# Mother_Board_Connectors.net
KiCad netlist of a schematic drawn in Altium Designer
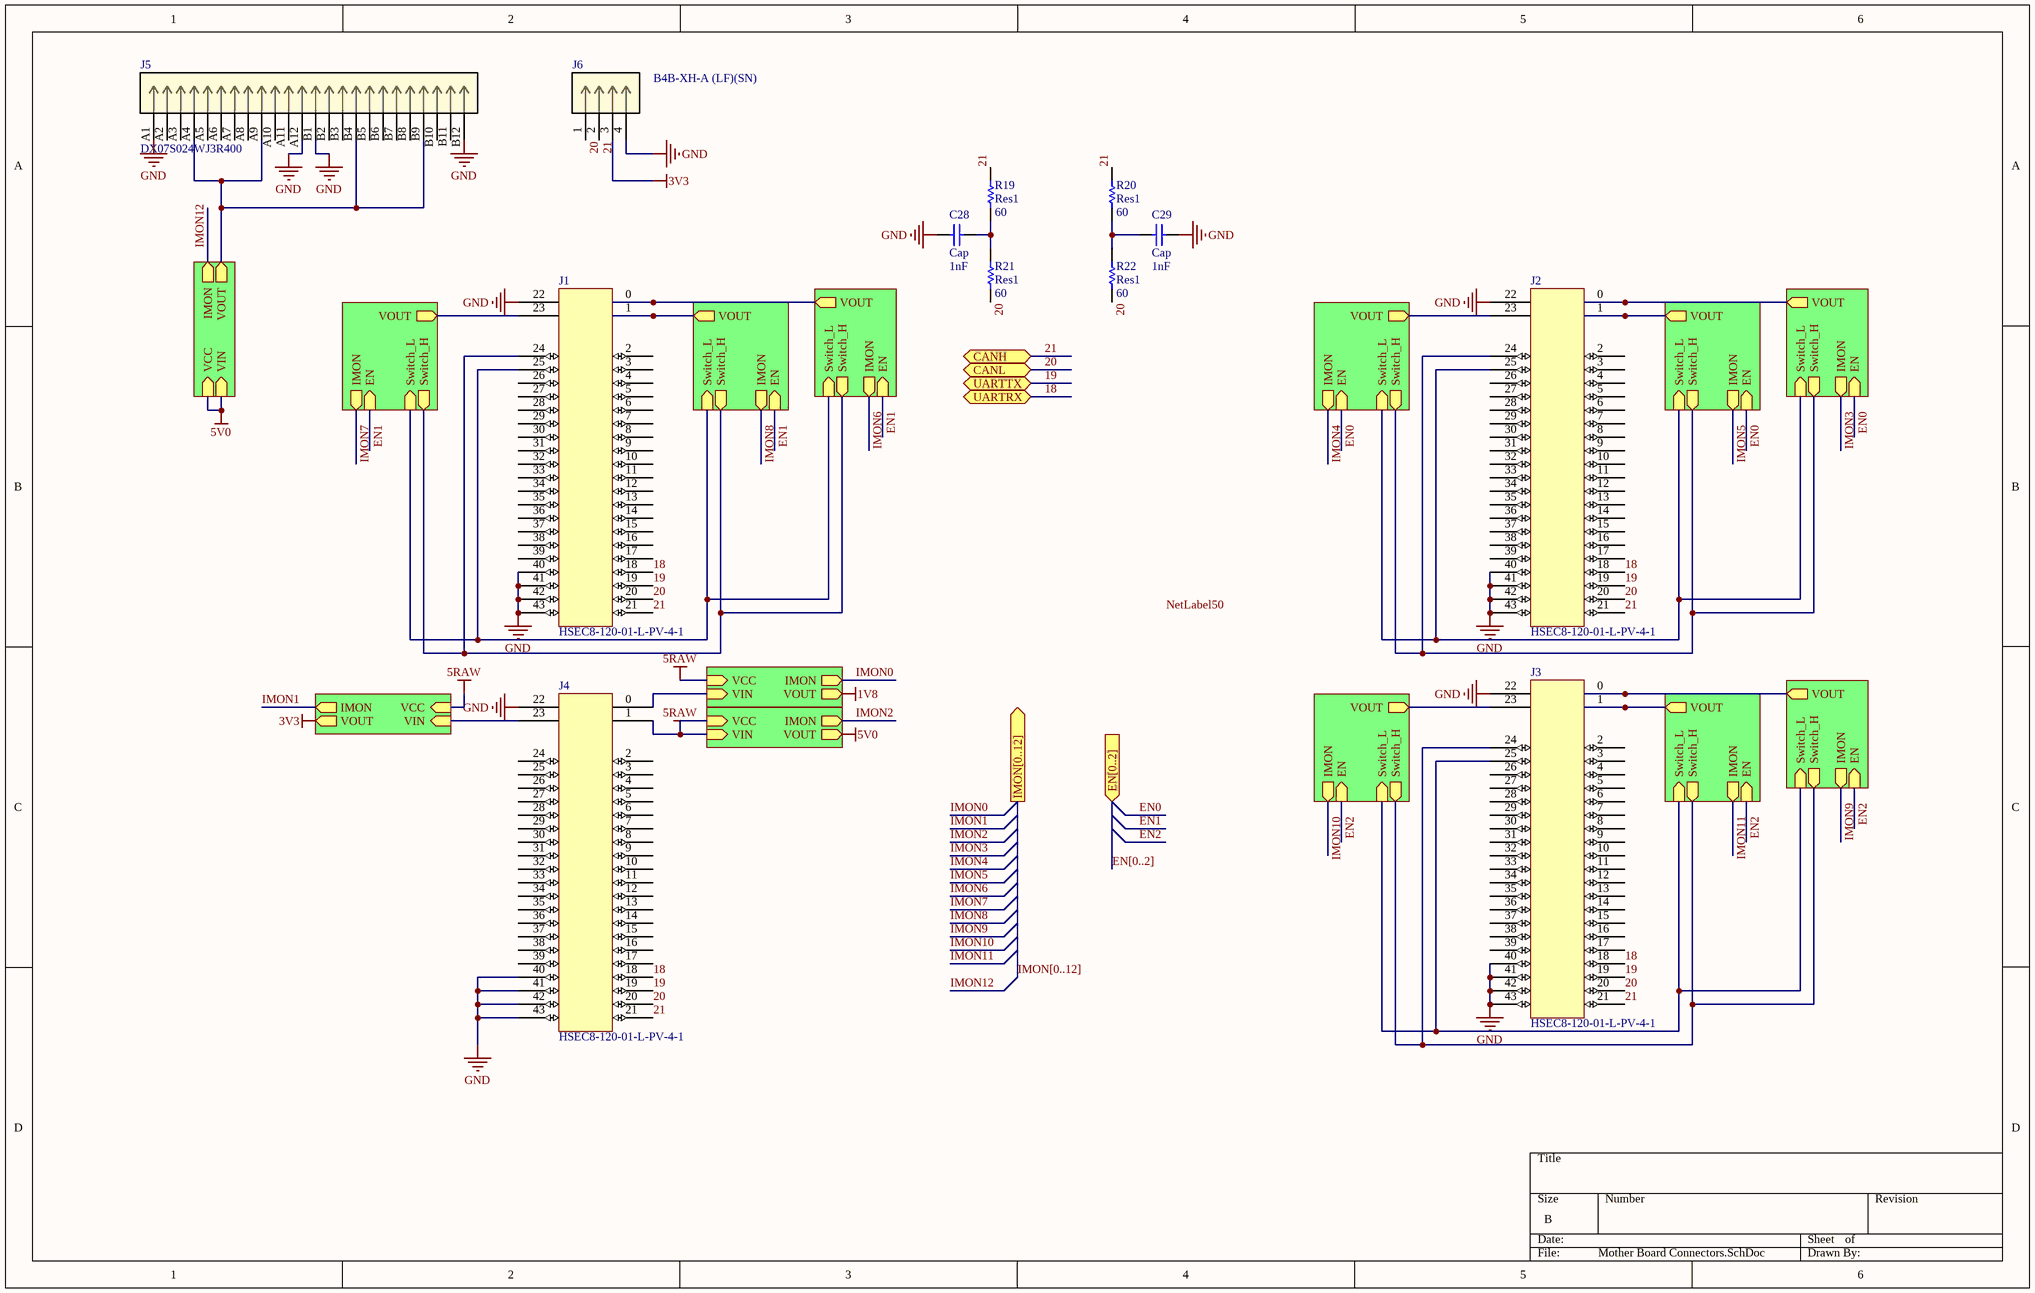
[diagram p0: Mother Board Connectors.SchDoc]

(export (version "E")
  (design (tool "Eeschema 10.0.6"))
  (components
    (comp (ref "C28")
      (value "Cap")
      (footprint "1608[0603]")
      (description "Capacitor")
      (fields (field (name "ALTIUM_VALUE") "1nF") (field (name "PUBLISHER") "Altium Limited"))
      (libsource (lib "Miscellaneous Devices") (part "Cap"))
    )
    (comp (ref "C29")
      (value "Cap")
      (footprint "1608[0603]")
      (description "Capacitor")
      (fields (field (name "ALTIUM_VALUE") "1nF") (field (name "PUBLISHER") "Altium Limited"))
      (libsource (lib "Miscellaneous Devices") (part "Cap"))
    )
    (comp (ref "J1")
      (value "HSEC8-120-01-L-PV-4-1")
      (footprint "HSEC8-120-01-L-PV-4-1")
      (libsource (lib "Edge Connector") (part "HSEC8-120-01-L-PV-4-1"))
    )
    (comp (ref "J2")
      (value "HSEC8-120-01-L-PV-4-1")
      (footprint "HSEC8-120-01-L-PV-4-1")
      (libsource (lib "Edge Connector") (part "HSEC8-120-01-L-PV-4-1"))
    )
    (comp (ref "J3")
      (value "HSEC8-120-01-L-PV-4-1")
      (footprint "HSEC8-120-01-L-PV-4-1")
      (libsource (lib "Edge Connector") (part "HSEC8-120-01-L-PV-4-1"))
    )
    (comp (ref "J4")
      (value "HSEC8-120-01-L-PV-4-1")
      (footprint "HSEC8-120-01-L-PV-4-1")
      (libsource (lib "Edge Connector") (part "HSEC8-120-01-L-PV-4-1"))
    )
    (comp (ref "J5")
      (value "DX07S024WJ3R400")
      (footprint "CONN_DX07S024WJ1R350_JAE")
      (description "No Description Available")
      (fields (field (name "COPYRIGHT") "Copyright (C) 2018 Accelerated Designs. All rights reserved"))
      (libsource (lib "DX07S024WJ3R400") (part "DX07S024WJ3R400"))
    )
    (comp (ref "J6")
      (value "B4B-XH-A (LF)(SN)")
      (footprint "CONN_B4B-XH-A (LF)(SN)_JST")
      (description "No Description Available")
      (fields (field (name "COPYRIGHT") "Copyright (C) 2018 Accelerated Designs. All rights reserved"))
      (libsource (lib "ABC motor conn") (part "B4B-XH-A (LF)(SN)"))
    )
    (comp (ref "R19")
      (value "Res1")
      (footprint "0402-A")
      (description "Resistor")
      (fields (field (name "ALTIUM_VALUE") "60") (field (name "PUBLISHER") "Altium Limited"))
      (libsource (lib "Miscellaneous Devices") (part "Res1"))
    )
    (comp (ref "R20")
      (value "Res1")
      (footprint "0402-A")
      (description "Resistor")
      (fields (field (name "ALTIUM_VALUE") "60") (field (name "PUBLISHER") "Altium Limited"))
      (libsource (lib "Miscellaneous Devices") (part "Res1"))
    )
    (comp (ref "R21")
      (value "Res1")
      (footprint "0402-A")
      (description "Resistor")
      (fields (field (name "ALTIUM_VALUE") "60") (field (name "PUBLISHER") "Altium Limited"))
      (libsource (lib "Miscellaneous Devices") (part "Res1"))
    )
    (comp (ref "R22")
      (value "Res1")
      (footprint "0402-A")
      (description "Resistor")
      (fields (field (name "ALTIUM_VALUE") "60") (field (name "PUBLISHER") "Altium Limited"))
      (libsource (lib "Miscellaneous Devices") (part "Res1"))
    )
  )
  (nets
    (net (code "1") (name "/18") (class "Default")
      (node (ref "J1") (pin "18") (pinfunction "0_18") (pintype "bidirectional"))
      (node (ref "J2") (pin "18") (pinfunction "0_18") (pintype "bidirectional"))
      (node (ref "J3") (pin "18") (pinfunction "0_18") (pintype "bidirectional"))
      (node (ref "J4") (pin "18") (pinfunction "0_18") (pintype "bidirectional"))
    )
    (net (code "2") (name "/19") (class "Default")
      (node (ref "J1") (pin "19") (pinfunction "0_19") (pintype "bidirectional"))
      (node (ref "J2") (pin "19") (pinfunction "0_19") (pintype "bidirectional"))
      (node (ref "J3") (pin "19") (pinfunction "0_19") (pintype "bidirectional"))
      (node (ref "J4") (pin "19") (pinfunction "0_19") (pintype "bidirectional"))
    )
    (net (code "3") (name "/20") (class "Default")
      (node (ref "J1") (pin "20") (pinfunction "0_20") (pintype "bidirectional"))
      (node (ref "J2") (pin "20") (pinfunction "0_20") (pintype "bidirectional"))
      (node (ref "J3") (pin "20") (pinfunction "0_20") (pintype "bidirectional"))
      (node (ref "J4") (pin "20") (pinfunction "0_20") (pintype "bidirectional"))
      (node (ref "J6") (pin "1") (pinfunction "1_1") (pintype "passive"))
      (node (ref "R21") (pin "1") (pinfunction "1_1") (pintype "passive"))
      (node (ref "R22") (pin "1") (pinfunction "1_1") (pintype "passive"))
    )
    (net (code "4") (name "/21") (class "Default")
      (node (ref "J1") (pin "21") (pinfunction "0_21") (pintype "bidirectional"))
      (node (ref "J2") (pin "21") (pinfunction "0_21") (pintype "bidirectional"))
      (node (ref "J3") (pin "21") (pinfunction "0_21") (pintype "bidirectional"))
      (node (ref "J4") (pin "21") (pinfunction "0_21") (pintype "bidirectional"))
      (node (ref "J6") (pin "2") (pinfunction "2_2") (pintype "passive"))
      (node (ref "R19") (pin "2") (pinfunction "2_2") (pintype "passive"))
      (node (ref "R20") (pin "2") (pinfunction "2_2") (pintype "passive"))
    )
    (net (code "24") (name "/Switch_H") (class "Default")
      (node (ref "J2") (pin "24") (pinfunction "24_24") (pintype "bidirectional"))
    )
    (net (code "25") (name "/Switch_H_1") (class "Default")
      (node (ref "J1") (pin "24") (pinfunction "24_24") (pintype "bidirectional"))
    )
    (net (code "26") (name "/Switch_H_2") (class "Default")
      (node (ref "J3") (pin "24") (pinfunction "24_24") (pintype "bidirectional"))
    )
    (net (code "27") (name "/Switch_L") (class "Default")
      (node (ref "J2") (pin "25") (pinfunction "25_25") (pintype "bidirectional"))
    )
    (net (code "28") (name "/Switch_L_1") (class "Default")
      (node (ref "J1") (pin "25") (pinfunction "25_25") (pintype "bidirectional"))
    )
    (net (code "29") (name "/Switch_L_2") (class "Default")
      (node (ref "J3") (pin "25") (pinfunction "25_25") (pintype "bidirectional"))
    )
    (net (code "30") (name "/VIN") (class "Default")
      (node (ref "J4") (pin "0") (pinfunction "0_0") (pintype "power_in"))
    )
    (net (code "31") (name "/VIN_1") (class "Default")
      (node (ref "J4") (pin "23") (pinfunction "23_23") (pintype "power_in"))
    )
    (net (code "32") (name "/VOUT") (class "Default")
      (node (ref "J1") (pin "0") (pinfunction "0_0") (pintype "power_in"))
    )
    (net (code "33") (name "/VOUT_1") (class "Default")
      (node (ref "J5") (pin "A4") (pinfunction "B11_A4") (pintype "passive"))
      (node (ref "J5") (pin "A9") (pinfunction "A5_A9") (pintype "passive"))
      (node (ref "J5") (pin "B4") (pinfunction "B5_B4") (pintype "passive"))
      (node (ref "J5") (pin "B9") (pinfunction "A11_B9") (pintype "passive"))
    )
    (net (code "34") (name "/VOUT_2") (class "Default")
      (node (ref "J3") (pin "23") (pinfunction "23_23") (pintype "power_in"))
    )
    (net (code "35") (name "/VOUT_3") (class "Default")
      (node (ref "J2") (pin "1") (pinfunction "0_1") (pintype "power_in"))
    )
    (net (code "36") (name "/VOUT_4") (class "Default")
      (node (ref "J3") (pin "1") (pinfunction "0_1") (pintype "power_in"))
    )
    (net (code "37") (name "/VOUT_5") (class "Default")
      (node (ref "J2") (pin "0") (pinfunction "0_0") (pintype "power_in"))
    )
    (net (code "38") (name "/VOUT_6") (class "Default")
      (node (ref "J3") (pin "0") (pinfunction "0_0") (pintype "power_in"))
    )
    (net (code "39") (name "/VOUT_7") (class "Default")
      (node (ref "J2") (pin "23") (pinfunction "23_23") (pintype "power_in"))
    )
    (net (code "40") (name "/VOUT_8") (class "Default")
      (node (ref "J1") (pin "23") (pinfunction "23_23") (pintype "power_in"))
    )
    (net (code "41") (name "/VOUT_9") (class "Default")
      (node (ref "J1") (pin "1") (pinfunction "0_1") (pintype "power_in"))
    )
    (net (code "43") (name "3V3") (class "Default")
      (node (ref "J6") (pin "3") (pinfunction "3_3") (pintype "passive"))
    )
    (net (code "44") (name "5RAW") (class "Default")
      (node (ref "J4") (pin "1") (pinfunction "0_1") (pintype "power_in"))
    )
    (net (code "46") (name "GND") (class "Default")
      (node (ref "C28") (pin "2") (pinfunction "2_2") (pintype "passive"))
      (node (ref "C29") (pin "1") (pinfunction "1_1") (pintype "passive"))
      (node (ref "J1") (pin "22") (pinfunction "0_22") (pintype "power_in"))
      (node (ref "J1") (pin "40") (pinfunction "40_40") (pintype "bidirectional"))
      (node (ref "J1") (pin "41") (pinfunction "41_41") (pintype "bidirectional"))
      (node (ref "J1") (pin "42") (pinfunction "42_42") (pintype "bidirectional"))
      (node (ref "J1") (pin "43") (pinfunction "43_43") (pintype "bidirectional"))
      (node (ref "J2") (pin "22") (pinfunction "0_22") (pintype "power_in"))
      (node (ref "J2") (pin "40") (pinfunction "40_40") (pintype "bidirectional"))
      (node (ref "J2") (pin "41") (pinfunction "41_41") (pintype "bidirectional"))
      (node (ref "J2") (pin "42") (pinfunction "42_42") (pintype "bidirectional"))
      (node (ref "J2") (pin "43") (pinfunction "43_43") (pintype "bidirectional"))
      (node (ref "J3") (pin "22") (pinfunction "0_22") (pintype "power_in"))
      (node (ref "J3") (pin "40") (pinfunction "40_40") (pintype "bidirectional"))
      (node (ref "J3") (pin "41") (pinfunction "41_41") (pintype "bidirectional"))
      (node (ref "J3") (pin "42") (pinfunction "42_42") (pintype "bidirectional"))
      (node (ref "J3") (pin "43") (pinfunction "43_43") (pintype "bidirectional"))
      (node (ref "J4") (pin "22") (pinfunction "0_22") (pintype "power_in"))
      (node (ref "J4") (pin "40") (pinfunction "40_40") (pintype "bidirectional"))
      (node (ref "J4") (pin "41") (pinfunction "41_41") (pintype "bidirectional"))
      (node (ref "J4") (pin "42") (pinfunction "42_42") (pintype "bidirectional"))
      (node (ref "J4") (pin "43") (pinfunction "43_43") (pintype "bidirectional"))
      (node (ref "J5") (pin "A1") (pinfunction "A1_A1") (pintype "passive"))
      (node (ref "J5") (pin "A12") (pinfunction "B7_A12") (pintype "passive"))
      (node (ref "J5") (pin "B1") (pinfunction "A7_B1") (pintype "passive"))
      (node (ref "J5") (pin "B12") (pinfunction "B1_B12") (pintype "passive"))
      (node (ref "J6") (pin "4") (pinfunction "4_4") (pintype "passive"))
    )
    (net (code "47") (name "Net-(C28-Pad1)") (class "Default")
      (node (ref "C28") (pin "1") (pinfunction "1_1") (pintype "passive"))
      (node (ref "R19") (pin "1") (pinfunction "1_1") (pintype "passive"))
      (node (ref "R21") (pin "2") (pinfunction "2_2") (pintype "passive"))
    )
    (net (code "48") (name "Net-(C29-Pad2)") (class "Default")
      (node (ref "C29") (pin "2") (pinfunction "2_2") (pintype "passive"))
      (node (ref "R20") (pin "1") (pinfunction "1_1") (pintype "passive"))
      (node (ref "R22") (pin "2") (pinfunction "2_2") (pintype "passive"))
    )
    (net (code "49") (name "unconnected-(J1-0-Pad2)") (class "Default")
      (node (ref "J1") (pin "2") (pinfunction "0_2") (pintype "bidirectional"))
    )
    (net (code "50") (name "unconnected-(J1-0-Pad3)") (class "Default")
      (node (ref "J1") (pin "3") (pinfunction "0_3") (pintype "bidirectional"))
    )
    (net (code "51") (name "unconnected-(J1-0-Pad4)") (class "Default")
      (node (ref "J1") (pin "4") (pinfunction "0_4") (pintype "bidirectional"))
    )
    (net (code "52") (name "unconnected-(J1-0-Pad5)") (class "Default")
      (node (ref "J1") (pin "5") (pinfunction "0_5") (pintype "bidirectional"))
    )
    (net (code "53") (name "unconnected-(J1-0-Pad6)") (class "Default")
      (node (ref "J1") (pin "6") (pinfunction "0_6") (pintype "bidirectional"))
    )
    (net (code "54") (name "unconnected-(J1-0-Pad7)") (class "Default")
      (node (ref "J1") (pin "7") (pinfunction "0_7") (pintype "bidirectional"))
    )
    (net (code "55") (name "unconnected-(J1-0-Pad8)") (class "Default")
      (node (ref "J1") (pin "8") (pinfunction "0_8") (pintype "bidirectional"))
    )
    (net (code "56") (name "unconnected-(J1-0-Pad9)") (class "Default")
      (node (ref "J1") (pin "9") (pinfunction "0_9") (pintype "bidirectional"))
    )
    (net (code "57") (name "unconnected-(J1-0-Pad10)") (class "Default")
      (node (ref "J1") (pin "10") (pinfunction "0_10") (pintype "bidirectional"))
    )
    (net (code "58") (name "unconnected-(J1-0-Pad11)") (class "Default")
      (node (ref "J1") (pin "11") (pinfunction "0_11") (pintype "bidirectional"))
    )
    (net (code "59") (name "unconnected-(J1-0-Pad12)") (class "Default")
      (node (ref "J1") (pin "12") (pinfunction "0_12") (pintype "bidirectional"))
    )
    (net (code "60") (name "unconnected-(J1-0-Pad13)") (class "Default")
      (node (ref "J1") (pin "13") (pinfunction "0_13") (pintype "bidirectional"))
    )
    (net (code "61") (name "unconnected-(J1-0-Pad14)") (class "Default")
      (node (ref "J1") (pin "14") (pinfunction "0_14") (pintype "bidirectional"))
    )
    (net (code "62") (name "unconnected-(J1-0-Pad15)") (class "Default")
      (node (ref "J1") (pin "15") (pinfunction "0_15") (pintype "bidirectional"))
    )
    (net (code "63") (name "unconnected-(J1-0-Pad16)") (class "Default")
      (node (ref "J1") (pin "16") (pinfunction "0_16") (pintype "bidirectional"))
    )
    (net (code "64") (name "unconnected-(J1-0-Pad17)") (class "Default")
      (node (ref "J1") (pin "17") (pinfunction "0_17") (pintype "bidirectional"))
    )
    (net (code "65") (name "unconnected-(J1-Pad26)") (class "Default")
      (node (ref "J1") (pin "26") (pinfunction "26_26") (pintype "bidirectional"))
    )
    (net (code "66") (name "unconnected-(J1-Pad27)") (class "Default")
      (node (ref "J1") (pin "27") (pinfunction "27_27") (pintype "bidirectional"))
    )
    (net (code "67") (name "unconnected-(J1-Pad28)") (class "Default")
      (node (ref "J1") (pin "28") (pinfunction "28_28") (pintype "bidirectional"))
    )
    (net (code "68") (name "unconnected-(J1-Pad29)") (class "Default")
      (node (ref "J1") (pin "29") (pinfunction "29_29") (pintype "bidirectional"))
    )
    (net (code "69") (name "unconnected-(J1-Pad30)") (class "Default")
      (node (ref "J1") (pin "30") (pinfunction "30_30") (pintype "bidirectional"))
    )
    (net (code "70") (name "unconnected-(J1-Pad31)") (class "Default")
      (node (ref "J1") (pin "31") (pinfunction "31_31") (pintype "bidirectional"))
    )
    (net (code "71") (name "unconnected-(J1-Pad32)") (class "Default")
      (node (ref "J1") (pin "32") (pinfunction "32_32") (pintype "bidirectional"))
    )
    (net (code "72") (name "unconnected-(J1-Pad33)") (class "Default")
      (node (ref "J1") (pin "33") (pinfunction "33_33") (pintype "bidirectional"))
    )
    (net (code "73") (name "unconnected-(J1-Pad34)") (class "Default")
      (node (ref "J1") (pin "34") (pinfunction "34_34") (pintype "bidirectional"))
    )
    (net (code "74") (name "unconnected-(J1-Pad35)") (class "Default")
      (node (ref "J1") (pin "35") (pinfunction "35_35") (pintype "bidirectional"))
    )
    (net (code "75") (name "unconnected-(J1-Pad36)") (class "Default")
      (node (ref "J1") (pin "36") (pinfunction "36_36") (pintype "bidirectional"))
    )
    (net (code "76") (name "unconnected-(J1-Pad37)") (class "Default")
      (node (ref "J1") (pin "37") (pinfunction "37_37") (pintype "bidirectional"))
    )
    (net (code "77") (name "unconnected-(J1-Pad38)") (class "Default")
      (node (ref "J1") (pin "38") (pinfunction "38_38") (pintype "bidirectional"))
    )
    (net (code "78") (name "unconnected-(J1-Pad39)") (class "Default")
      (node (ref "J1") (pin "39") (pinfunction "39_39") (pintype "bidirectional"))
    )
    (net (code "79") (name "unconnected-(J2-0-Pad2)") (class "Default")
      (node (ref "J2") (pin "2") (pinfunction "0_2") (pintype "bidirectional"))
    )
    (net (code "80") (name "unconnected-(J2-0-Pad3)") (class "Default")
      (node (ref "J2") (pin "3") (pinfunction "0_3") (pintype "bidirectional"))
    )
    (net (code "81") (name "unconnected-(J2-0-Pad4)") (class "Default")
      (node (ref "J2") (pin "4") (pinfunction "0_4") (pintype "bidirectional"))
    )
    (net (code "82") (name "unconnected-(J2-0-Pad5)") (class "Default")
      (node (ref "J2") (pin "5") (pinfunction "0_5") (pintype "bidirectional"))
    )
    (net (code "83") (name "unconnected-(J2-0-Pad6)") (class "Default")
      (node (ref "J2") (pin "6") (pinfunction "0_6") (pintype "bidirectional"))
    )
    (net (code "84") (name "unconnected-(J2-0-Pad7)") (class "Default")
      (node (ref "J2") (pin "7") (pinfunction "0_7") (pintype "bidirectional"))
    )
    (net (code "85") (name "unconnected-(J2-0-Pad8)") (class "Default")
      (node (ref "J2") (pin "8") (pinfunction "0_8") (pintype "bidirectional"))
    )
    (net (code "86") (name "unconnected-(J2-0-Pad9)") (class "Default")
      (node (ref "J2") (pin "9") (pinfunction "0_9") (pintype "bidirectional"))
    )
    (net (code "87") (name "unconnected-(J2-0-Pad10)") (class "Default")
      (node (ref "J2") (pin "10") (pinfunction "0_10") (pintype "bidirectional"))
    )
    (net (code "88") (name "unconnected-(J2-0-Pad11)") (class "Default")
      (node (ref "J2") (pin "11") (pinfunction "0_11") (pintype "bidirectional"))
    )
    (net (code "89") (name "unconnected-(J2-0-Pad12)") (class "Default")
      (node (ref "J2") (pin "12") (pinfunction "0_12") (pintype "bidirectional"))
    )
    (net (code "90") (name "unconnected-(J2-0-Pad13)") (class "Default")
      (node (ref "J2") (pin "13") (pinfunction "0_13") (pintype "bidirectional"))
    )
    (net (code "91") (name "unconnected-(J2-0-Pad14)") (class "Default")
      (node (ref "J2") (pin "14") (pinfunction "0_14") (pintype "bidirectional"))
    )
    (net (code "92") (name "unconnected-(J2-0-Pad15)") (class "Default")
      (node (ref "J2") (pin "15") (pinfunction "0_15") (pintype "bidirectional"))
    )
    (net (code "93") (name "unconnected-(J2-0-Pad16)") (class "Default")
      (node (ref "J2") (pin "16") (pinfunction "0_16") (pintype "bidirectional"))
    )
    (net (code "94") (name "unconnected-(J2-0-Pad17)") (class "Default")
      (node (ref "J2") (pin "17") (pinfunction "0_17") (pintype "bidirectional"))
    )
    (net (code "95") (name "unconnected-(J2-Pad26)") (class "Default")
      (node (ref "J2") (pin "26") (pinfunction "26_26") (pintype "bidirectional"))
    )
    (net (code "96") (name "unconnected-(J2-Pad27)") (class "Default")
      (node (ref "J2") (pin "27") (pinfunction "27_27") (pintype "bidirectional"))
    )
    (net (code "97") (name "unconnected-(J2-Pad28)") (class "Default")
      (node (ref "J2") (pin "28") (pinfunction "28_28") (pintype "bidirectional"))
    )
    (net (code "98") (name "unconnected-(J2-Pad29)") (class "Default")
      (node (ref "J2") (pin "29") (pinfunction "29_29") (pintype "bidirectional"))
    )
    (net (code "99") (name "unconnected-(J2-Pad30)") (class "Default")
      (node (ref "J2") (pin "30") (pinfunction "30_30") (pintype "bidirectional"))
    )
    (net (code "100") (name "unconnected-(J2-Pad31)") (class "Default")
      (node (ref "J2") (pin "31") (pinfunction "31_31") (pintype "bidirectional"))
    )
    (net (code "101") (name "unconnected-(J2-Pad32)") (class "Default")
      (node (ref "J2") (pin "32") (pinfunction "32_32") (pintype "bidirectional"))
    )
    (net (code "102") (name "unconnected-(J2-Pad33)") (class "Default")
      (node (ref "J2") (pin "33") (pinfunction "33_33") (pintype "bidirectional"))
    )
    (net (code "103") (name "unconnected-(J2-Pad34)") (class "Default")
      (node (ref "J2") (pin "34") (pinfunction "34_34") (pintype "bidirectional"))
    )
    (net (code "104") (name "unconnected-(J2-Pad35)") (class "Default")
      (node (ref "J2") (pin "35") (pinfunction "35_35") (pintype "bidirectional"))
    )
    (net (code "105") (name "unconnected-(J2-Pad36)") (class "Default")
      (node (ref "J2") (pin "36") (pinfunction "36_36") (pintype "bidirectional"))
    )
    (net (code "106") (name "unconnected-(J2-Pad37)") (class "Default")
      (node (ref "J2") (pin "37") (pinfunction "37_37") (pintype "bidirectional"))
    )
    (net (code "107") (name "unconnected-(J2-Pad38)") (class "Default")
      (node (ref "J2") (pin "38") (pinfunction "38_38") (pintype "bidirectional"))
    )
    (net (code "108") (name "unconnected-(J2-Pad39)") (class "Default")
      (node (ref "J2") (pin "39") (pinfunction "39_39") (pintype "bidirectional"))
    )
    (net (code "109") (name "unconnected-(J3-0-Pad2)") (class "Default")
      (node (ref "J3") (pin "2") (pinfunction "0_2") (pintype "bidirectional"))
    )
    (net (code "110") (name "unconnected-(J3-0-Pad3)") (class "Default")
      (node (ref "J3") (pin "3") (pinfunction "0_3") (pintype "bidirectional"))
    )
    (net (code "111") (name "unconnected-(J3-0-Pad4)") (class "Default")
      (node (ref "J3") (pin "4") (pinfunction "0_4") (pintype "bidirectional"))
    )
    (net (code "112") (name "unconnected-(J3-0-Pad5)") (class "Default")
      (node (ref "J3") (pin "5") (pinfunction "0_5") (pintype "bidirectional"))
    )
    (net (code "113") (name "unconnected-(J3-0-Pad6)") (class "Default")
      (node (ref "J3") (pin "6") (pinfunction "0_6") (pintype "bidirectional"))
    )
    (net (code "114") (name "unconnected-(J3-0-Pad7)") (class "Default")
      (node (ref "J3") (pin "7") (pinfunction "0_7") (pintype "bidirectional"))
    )
    (net (code "115") (name "unconnected-(J3-0-Pad8)") (class "Default")
      (node (ref "J3") (pin "8") (pinfunction "0_8") (pintype "bidirectional"))
    )
    (net (code "116") (name "unconnected-(J3-0-Pad9)") (class "Default")
      (node (ref "J3") (pin "9") (pinfunction "0_9") (pintype "bidirectional"))
    )
    (net (code "117") (name "unconnected-(J3-0-Pad10)") (class "Default")
      (node (ref "J3") (pin "10") (pinfunction "0_10") (pintype "bidirectional"))
    )
    (net (code "118") (name "unconnected-(J3-0-Pad11)") (class "Default")
      (node (ref "J3") (pin "11") (pinfunction "0_11") (pintype "bidirectional"))
    )
    (net (code "119") (name "unconnected-(J3-0-Pad12)") (class "Default")
      (node (ref "J3") (pin "12") (pinfunction "0_12") (pintype "bidirectional"))
    )
    (net (code "120") (name "unconnected-(J3-0-Pad13)") (class "Default")
      (node (ref "J3") (pin "13") (pinfunction "0_13") (pintype "bidirectional"))
    )
    (net (code "121") (name "unconnected-(J3-0-Pad14)") (class "Default")
      (node (ref "J3") (pin "14") (pinfunction "0_14") (pintype "bidirectional"))
    )
    (net (code "122") (name "unconnected-(J3-0-Pad15)") (class "Default")
      (node (ref "J3") (pin "15") (pinfunction "0_15") (pintype "bidirectional"))
    )
    (net (code "123") (name "unconnected-(J3-0-Pad16)") (class "Default")
      (node (ref "J3") (pin "16") (pinfunction "0_16") (pintype "bidirectional"))
    )
    (net (code "124") (name "unconnected-(J3-0-Pad17)") (class "Default")
      (node (ref "J3") (pin "17") (pinfunction "0_17") (pintype "bidirectional"))
    )
    (net (code "125") (name "unconnected-(J3-Pad26)") (class "Default")
      (node (ref "J3") (pin "26") (pinfunction "26_26") (pintype "bidirectional"))
    )
    (net (code "126") (name "unconnected-(J3-Pad27)") (class "Default")
      (node (ref "J3") (pin "27") (pinfunction "27_27") (pintype "bidirectional"))
    )
    (net (code "127") (name "unconnected-(J3-Pad28)") (class "Default")
      (node (ref "J3") (pin "28") (pinfunction "28_28") (pintype "bidirectional"))
    )
    (net (code "128") (name "unconnected-(J3-Pad29)") (class "Default")
      (node (ref "J3") (pin "29") (pinfunction "29_29") (pintype "bidirectional"))
    )
    (net (code "129") (name "unconnected-(J3-Pad30)") (class "Default")
      (node (ref "J3") (pin "30") (pinfunction "30_30") (pintype "bidirectional"))
    )
    (net (code "130") (name "unconnected-(J3-Pad31)") (class "Default")
      (node (ref "J3") (pin "31") (pinfunction "31_31") (pintype "bidirectional"))
    )
    (net (code "131") (name "unconnected-(J3-Pad32)") (class "Default")
      (node (ref "J3") (pin "32") (pinfunction "32_32") (pintype "bidirectional"))
    )
    (net (code "132") (name "unconnected-(J3-Pad33)") (class "Default")
      (node (ref "J3") (pin "33") (pinfunction "33_33") (pintype "bidirectional"))
    )
    (net (code "133") (name "unconnected-(J3-Pad34)") (class "Default")
      (node (ref "J3") (pin "34") (pinfunction "34_34") (pintype "bidirectional"))
    )
    (net (code "134") (name "unconnected-(J3-Pad35)") (class "Default")
      (node (ref "J3") (pin "35") (pinfunction "35_35") (pintype "bidirectional"))
    )
    (net (code "135") (name "unconnected-(J3-Pad36)") (class "Default")
      (node (ref "J3") (pin "36") (pinfunction "36_36") (pintype "bidirectional"))
    )
    (net (code "136") (name "unconnected-(J3-Pad37)") (class "Default")
      (node (ref "J3") (pin "37") (pinfunction "37_37") (pintype "bidirectional"))
    )
    (net (code "137") (name "unconnected-(J3-Pad38)") (class "Default")
      (node (ref "J3") (pin "38") (pinfunction "38_38") (pintype "bidirectional"))
    )
    (net (code "138") (name "unconnected-(J3-Pad39)") (class "Default")
      (node (ref "J3") (pin "39") (pinfunction "39_39") (pintype "bidirectional"))
    )
    (net (code "139") (name "unconnected-(J4-0-Pad2)") (class "Default")
      (node (ref "J4") (pin "2") (pinfunction "0_2") (pintype "bidirectional"))
    )
    (net (code "140") (name "unconnected-(J4-0-Pad3)") (class "Default")
      (node (ref "J4") (pin "3") (pinfunction "0_3") (pintype "bidirectional"))
    )
    (net (code "141") (name "unconnected-(J4-0-Pad4)") (class "Default")
      (node (ref "J4") (pin "4") (pinfunction "0_4") (pintype "bidirectional"))
    )
    (net (code "142") (name "unconnected-(J4-0-Pad5)") (class "Default")
      (node (ref "J4") (pin "5") (pinfunction "0_5") (pintype "bidirectional"))
    )
    (net (code "143") (name "unconnected-(J4-0-Pad6)") (class "Default")
      (node (ref "J4") (pin "6") (pinfunction "0_6") (pintype "bidirectional"))
    )
    (net (code "144") (name "unconnected-(J4-0-Pad7)") (class "Default")
      (node (ref "J4") (pin "7") (pinfunction "0_7") (pintype "bidirectional"))
    )
    (net (code "145") (name "unconnected-(J4-0-Pad8)") (class "Default")
      (node (ref "J4") (pin "8") (pinfunction "0_8") (pintype "bidirectional"))
    )
    (net (code "146") (name "unconnected-(J4-0-Pad9)") (class "Default")
      (node (ref "J4") (pin "9") (pinfunction "0_9") (pintype "bidirectional"))
    )
    (net (code "147") (name "unconnected-(J4-0-Pad10)") (class "Default")
      (node (ref "J4") (pin "10") (pinfunction "0_10") (pintype "bidirectional"))
    )
    (net (code "148") (name "unconnected-(J4-0-Pad11)") (class "Default")
      (node (ref "J4") (pin "11") (pinfunction "0_11") (pintype "bidirectional"))
    )
    (net (code "149") (name "unconnected-(J4-0-Pad12)") (class "Default")
      (node (ref "J4") (pin "12") (pinfunction "0_12") (pintype "bidirectional"))
    )
    (net (code "150") (name "unconnected-(J4-0-Pad13)") (class "Default")
      (node (ref "J4") (pin "13") (pinfunction "0_13") (pintype "bidirectional"))
    )
    (net (code "151") (name "unconnected-(J4-0-Pad14)") (class "Default")
      (node (ref "J4") (pin "14") (pinfunction "0_14") (pintype "bidirectional"))
    )
    (net (code "152") (name "unconnected-(J4-0-Pad15)") (class "Default")
      (node (ref "J4") (pin "15") (pinfunction "0_15") (pintype "bidirectional"))
    )
    (net (code "153") (name "unconnected-(J4-0-Pad16)") (class "Default")
      (node (ref "J4") (pin "16") (pinfunction "0_16") (pintype "bidirectional"))
    )
    (net (code "154") (name "unconnected-(J4-0-Pad17)") (class "Default")
      (node (ref "J4") (pin "17") (pinfunction "0_17") (pintype "bidirectional"))
    )
    (net (code "155") (name "unconnected-(J4-Pad24)") (class "Default")
      (node (ref "J4") (pin "24") (pinfunction "24_24") (pintype "bidirectional"))
    )
    (net (code "156") (name "unconnected-(J4-Pad25)") (class "Default")
      (node (ref "J4") (pin "25") (pinfunction "25_25") (pintype "bidirectional"))
    )
    (net (code "157") (name "unconnected-(J4-Pad26)") (class "Default")
      (node (ref "J4") (pin "26") (pinfunction "26_26") (pintype "bidirectional"))
    )
    (net (code "158") (name "unconnected-(J4-Pad27)") (class "Default")
      (node (ref "J4") (pin "27") (pinfunction "27_27") (pintype "bidirectional"))
    )
    (net (code "159") (name "unconnected-(J4-Pad28)") (class "Default")
      (node (ref "J4") (pin "28") (pinfunction "28_28") (pintype "bidirectional"))
    )
    (net (code "160") (name "unconnected-(J4-Pad29)") (class "Default")
      (node (ref "J4") (pin "29") (pinfunction "29_29") (pintype "bidirectional"))
    )
    (net (code "161") (name "unconnected-(J4-Pad30)") (class "Default")
      (node (ref "J4") (pin "30") (pinfunction "30_30") (pintype "bidirectional"))
    )
    (net (code "162") (name "unconnected-(J4-Pad31)") (class "Default")
      (node (ref "J4") (pin "31") (pinfunction "31_31") (pintype "bidirectional"))
    )
    (net (code "163") (name "unconnected-(J4-Pad32)") (class "Default")
      (node (ref "J4") (pin "32") (pinfunction "32_32") (pintype "bidirectional"))
    )
    (net (code "164") (name "unconnected-(J4-Pad33)") (class "Default")
      (node (ref "J4") (pin "33") (pinfunction "33_33") (pintype "bidirectional"))
    )
    (net (code "165") (name "unconnected-(J4-Pad34)") (class "Default")
      (node (ref "J4") (pin "34") (pinfunction "34_34") (pintype "bidirectional"))
    )
    (net (code "166") (name "unconnected-(J4-Pad35)") (class "Default")
      (node (ref "J4") (pin "35") (pinfunction "35_35") (pintype "bidirectional"))
    )
    (net (code "167") (name "unconnected-(J4-Pad36)") (class "Default")
      (node (ref "J4") (pin "36") (pinfunction "36_36") (pintype "bidirectional"))
    )
    (net (code "168") (name "unconnected-(J4-Pad37)") (class "Default")
      (node (ref "J4") (pin "37") (pinfunction "37_37") (pintype "bidirectional"))
    )
    (net (code "169") (name "unconnected-(J4-Pad38)") (class "Default")
      (node (ref "J4") (pin "38") (pinfunction "38_38") (pintype "bidirectional"))
    )
    (net (code "170") (name "unconnected-(J4-Pad39)") (class "Default")
      (node (ref "J4") (pin "39") (pinfunction "39_39") (pintype "bidirectional"))
    )
    (net (code "171") (name "unconnected-(J5-A2-PadA3)") (class "Default")
      (node (ref "J5") (pin "A3") (pinfunction "A2_A3") (pintype "passive"))
    )
    (net (code "172") (name "unconnected-(J5-A3-PadA5)") (class "Default")
      (node (ref "J5") (pin "A5") (pinfunction "A3_A5") (pintype "passive"))
    )
    (net (code "173") (name "unconnected-(J5-A4-PadA7)") (class "Default")
      (node (ref "J5") (pin "A7") (pinfunction "A4_A7") (pintype "passive"))
    )
    (net (code "174") (name "unconnected-(J5-A6-PadA11)") (class "Default")
      (node (ref "J5") (pin "A11") (pinfunction "A6_A11") (pintype "passive"))
    )
    (net (code "175") (name "unconnected-(J5-A8-PadB3)") (class "Default")
      (node (ref "J5") (pin "B3") (pinfunction "A8_B3") (pintype "passive"))
    )
    (net (code "176") (name "unconnected-(J5-A9-PadB5)") (class "Default")
      (node (ref "J5") (pin "B5") (pinfunction "A9_B5") (pintype "passive"))
    )
    (net (code "177") (name "unconnected-(J5-A10-PadB7)") (class "Default")
      (node (ref "J5") (pin "B7") (pinfunction "A10_B7") (pintype "passive"))
    )
    (net (code "178") (name "unconnected-(J5-A12-PadB11)") (class "Default")
      (node (ref "J5") (pin "B11") (pinfunction "A12_B11") (pintype "passive"))
    )
    (net (code "179") (name "unconnected-(J5-B2-PadB10)") (class "Default")
      (node (ref "J5") (pin "B10") (pinfunction "B2_B10") (pintype "passive"))
    )
    (net (code "180") (name "unconnected-(J5-B3-PadB8)") (class "Default")
      (node (ref "J5") (pin "B8") (pinfunction "B3_B8") (pintype "passive"))
    )
    (net (code "181") (name "unconnected-(J5-B4-PadB6)") (class "Default")
      (node (ref "J5") (pin "B6") (pinfunction "B4_B6") (pintype "passive"))
    )
    (net (code "182") (name "unconnected-(J5-B6-PadB2)") (class "Default")
      (node (ref "J5") (pin "B2") (pinfunction "B6_B2") (pintype "passive"))
    )
    (net (code "183") (name "unconnected-(J5-B8-PadA10)") (class "Default")
      (node (ref "J5") (pin "A10") (pinfunction "B8_A10") (pintype "passive"))
    )
    (net (code "184") (name "unconnected-(J5-B9-PadA8)") (class "Default")
      (node (ref "J5") (pin "A8") (pinfunction "B9_A8") (pintype "passive"))
    )
    (net (code "185") (name "unconnected-(J5-B10-PadA6)") (class "Default")
      (node (ref "J5") (pin "A6") (pinfunction "B10_A6") (pintype "passive"))
    )
    (net (code "186") (name "unconnected-(J5-B12-PadA2)") (class "Default")
      (node (ref "J5") (pin "A2") (pinfunction "B12_A2") (pintype "passive"))
    )
  )
)
